# mic.net
KiCad netlist of a schematic drawn in Altium Designer
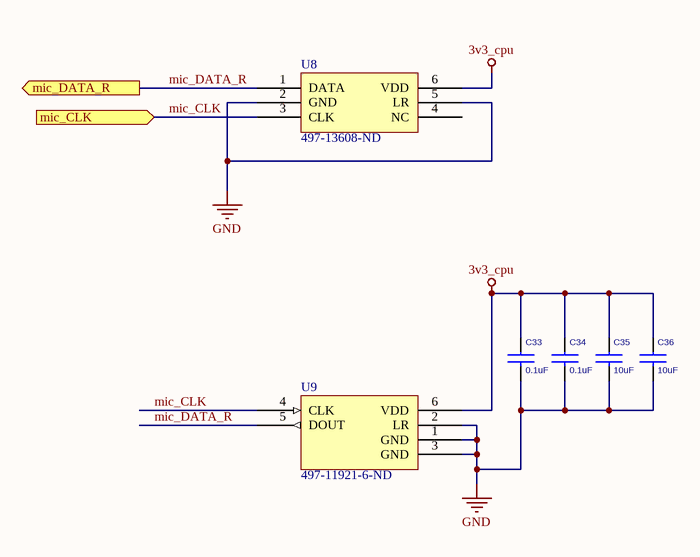
[diagram p0: mic.SchDoc]

(export (version "E")
  (design (tool "Eeschema 10.0.6"))
  (components
    (comp (ref "C33")
      (value "0.1uF")
      (footprint "CAPC2012X09M")
      (description "CAP CER 0.1UF 25V 10% X7R 0805")
      (libsource (lib "Capacitors") (part "CAP_SMD_0.1UF_10%"))
    )
    (comp (ref "C34")
      (value "0.1uF")
      (footprint "CAPC2012X09M")
      (description "CAP CER 0.1UF 25V 10% X7R 0805")
      (libsource (lib "Capacitors") (part "CAP_SMD_0.1UF_10%"))
    )
    (comp (ref "C35")
      (value "10uF")
      (footprint "CAPC2012X09M")
      (description "CAP CER 10UF 16V 20% X5R 0805")
      (libsource (lib "Capacitors") (part "CAP_SMD_10UF_20%"))
    )
    (comp (ref "C36")
      (value "10uF")
      (footprint "CAPC2012X09M")
      (description "CAP CER 10UF 16V 20% X5R 0805")
      (libsource (lib "Capacitors") (part "CAP_SMD_10UF_20%"))
    )
    (comp (ref "U8")
      (value "STEVAL-MKI129V1")
      (footprint "STEVAL-MKI129V1")
      (fields (field (name "SUPPLIER PART NUMBER 1") "497-13608-ND"))
      (libsource (lib "TruthEar") (part "STEVAL-MKI129V1"))
    )
    (comp (ref "U9")
      (value "MP45DT02")
      (footprint "LGA6C165P2X3_376X472X125")
      (fields (field (name "SUPPLIER PART NUMBER 1") "497-11921-6-ND"))
      (libsource (lib "TruthEar") (part "MP45DT02"))
    )
  )
  (nets
    (net (code "1") (name "/mic_CLK") (class "Default")
      (node (ref "U8") (pin "3") (pinfunction "CLK_3") (pintype "power_in"))
      (node (ref "U9") (pin "4") (pinfunction "CLK_4") (pintype "input"))
    )
    (net (code "2") (name "/mic_DATA_R") (class "Default")
      (node (ref "U8") (pin "1") (pinfunction "DATA_1") (pintype "power_in"))
      (node (ref "U9") (pin "5") (pinfunction "DOUT_5") (pintype "output"))
    )
    (net (code "3") (name "3v3_cpu") (class "Default")
      (node (ref "C33") (pin "1") (pinfunction "1_1") (pintype "passive"))
      (node (ref "C34") (pin "1") (pinfunction "1_1") (pintype "passive"))
      (node (ref "C35") (pin "1") (pinfunction "1_1") (pintype "passive"))
      (node (ref "C36") (pin "1") (pinfunction "1_1") (pintype "passive"))
      (node (ref "U8") (pin "6") (pinfunction "VDD_6") (pintype "power_in"))
      (node (ref "U9") (pin "6") (pinfunction "VDD_6") (pintype "power_in"))
    )
    (net (code "4") (name "GND") (class "Default")
      (node (ref "C33") (pin "2") (pinfunction "2_2") (pintype "passive"))
      (node (ref "C34") (pin "2") (pinfunction "2_2") (pintype "passive"))
      (node (ref "C35") (pin "2") (pinfunction "2_2") (pintype "passive"))
      (node (ref "C36") (pin "2") (pinfunction "2_2") (pintype "passive"))
      (node (ref "U8") (pin "2") (pinfunction "GND_2") (pintype "power_in"))
      (node (ref "U8") (pin "5") (pinfunction "LR_5") (pintype "power_in"))
      (node (ref "U9") (pin "1") (pinfunction "GND_1") (pintype "power_in"))
      (node (ref "U9") (pin "2") (pinfunction "LR_2") (pintype "power_in"))
      (node (ref "U9") (pin "3") (pinfunction "GND_3") (pintype "power_in"))
    )
    (net (code "5") (name "unconnected-(U8-NC-Pad4)") (class "Default")
      (node (ref "U8") (pin "4") (pinfunction "NC_4") (pintype "power_in"))
    )
  )
)
